# urbansensor.net
KiCad netlist of a schematic drawn in EAGLE
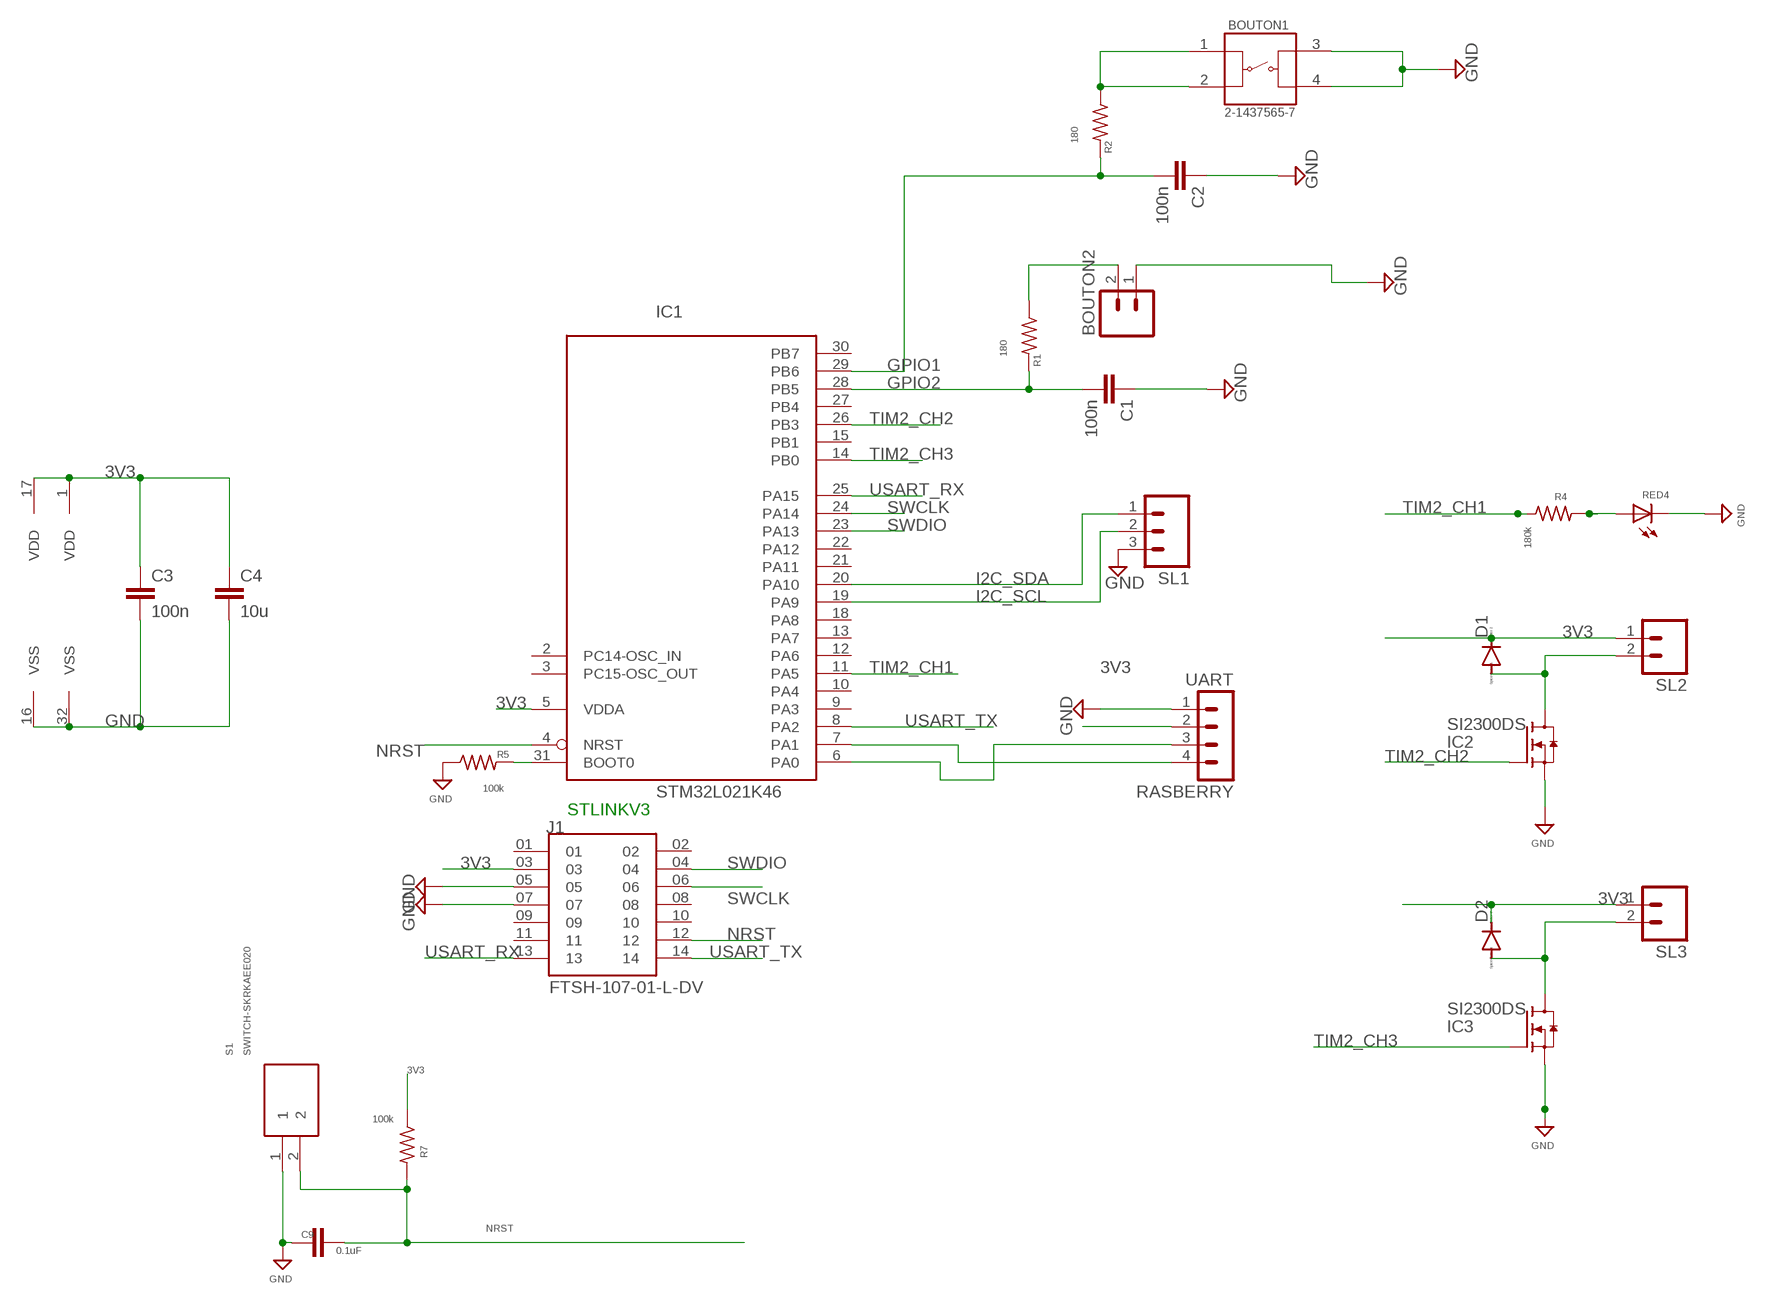
[diagram p0: schematic, sheet 1]

(export (version "E")
  (design (tool "Eeschema 10.0.6"))
  (components
    (comp (ref "BOUTON1")
      (value "2-1437565-7")
      (footprint "eagle-import:SW_2-1437565-7")
      (fields (field (name "MF") "TE Connectivity") (field (name "MP") "FSM2JSMA"))
      (libsource (lib "eagle-import") (part "2-1437565-7"))
    )
    (comp (ref "BOUTON2")
      (value "MA02")
      (footprint "eagle-import:02PA")
      (libsource (lib "eagle-import") (part "MA02"))
    )
    (comp (ref "C1")
      (value "100n")
      (footprint "eagle-import:C0805")
      (libsource (lib "eagle-import") (part "C-EUC0805"))
    )
    (comp (ref "C2")
      (value "100n")
      (footprint "eagle-import:C0805")
      (libsource (lib "eagle-import") (part "C-EUC0805"))
    )
    (comp (ref "C3")
      (value "100n")
      (footprint "eagle-import:C0805")
      (libsource (lib "eagle-import") (part "C-EUC0805"))
    )
    (comp (ref "C4")
      (value "10u")
      (footprint "eagle-import:C1210")
      (libsource (lib "eagle-import") (part "C-EUC1210"))
    )
    (comp (ref "C9")
      (value "0.1uF")
      (footprint "eagle-import:1206")
      (libsource (lib "eagle-import") (part "PASSIF-CAP-1206"))
    )
    (comp (ref "D1")
      (value "DIODE-SOD523")
      (footprint "eagle-import:SOD523")
      (libsource (lib "eagle-import") (part "DIODE-SOD523"))
    )
    (comp (ref "D2")
      (value "DIODE-SOD523")
      (footprint "eagle-import:SOD523")
      (libsource (lib "eagle-import") (part "DIODE-SOD523"))
    )
    (comp (ref "IC1")
      (value "STM32L021K46")
      (footprint "eagle-import:LQFP32")
      (libsource (lib "eagle-import") (part "STM32L021K46"))
    )
    (comp (ref "IC2")
      (value "SI2300DS")
      (footprint "eagle-import:SOT23")
      (libsource (lib "eagle-import") (part "SI2300DS"))
    )
    (comp (ref "IC3")
      (value "SI2300DS")
      (footprint "eagle-import:SOT23")
      (libsource (lib "eagle-import") (part "SI2300DS"))
    )
    (comp (ref "J1")
      (value "FTSH-107-01-L-DV")
      (footprint "eagle-import:SAMTEC_FTSH-107-01-L-DV")
      (fields (field (name "MF") "Samtec"))
      (libsource (lib "eagle-import") (part "FTSH-107-01-L-DV"))
    )
    (comp (ref "R1")
      (value "180")
      (footprint "eagle-import:R0805")
      (libsource (lib "eagle-import") (part "R-US0805"))
    )
    (comp (ref "R2")
      (value "180")
      (footprint "eagle-import:R0805")
      (libsource (lib "eagle-import") (part "R-US0805"))
    )
    (comp (ref "R4")
      (value "180k")
      (footprint "eagle-import:R0805")
      (libsource (lib "eagle-import") (part "R-US0805"))
    )
    (comp (ref "R5")
      (value "100k")
      (footprint "eagle-import:R0805")
      (libsource (lib "eagle-import") (part "R-US0805"))
    )
    (comp (ref "R7")
      (value "100k")
      (footprint "eagle-import:R0805")
      (libsource (lib "eagle-import") (part "R-US0805"))
    )
    (comp (ref "RASBERRY")
      (value "UART")
      (footprint "eagle-import:MA04-1")
      (libsource (lib "eagle-import") (part "MA04-1"))
    )
    (comp (ref "RED4")
      (value "LED-0603")
      (footprint "eagle-import:0603-LED")
      (libsource (lib "eagle-import") (part "LED-0603"))
    )
    (comp (ref "S1")
      (value "SWITCH-SKRKAEE020")
      (footprint "eagle-import:SKRKAEE020")
      (fields
        (field (name "MANUFACTURER_PART_NUMBER") "SKRKAEE020")
        (field (name "MOUSER_PART_NUMBER") "688-SKRKAEE020")
      )
      (libsource (lib "eagle-import") (part "SWITCH-SKRKAEE020"))
    )
    (comp (ref "SL1")
      (value "MA03")
      (footprint "eagle-import:03P")
      (libsource (lib "eagle-import") (part "MA03"))
    )
    (comp (ref "SL2")
      (value "MA02")
      (footprint "eagle-import:02PA")
      (libsource (lib "eagle-import") (part "MA02"))
    )
    (comp (ref "SL3")
      (value "MA02")
      (footprint "eagle-import:02PA")
      (libsource (lib "eagle-import") (part "MA02"))
    )
  )
  (nets
    (net (code "1") (name "/3V3") (class "Default")
      (node (ref "C3") (pin "1") (pinfunction "1_1") (pintype "passive"))
      (node (ref "C4") (pin "1") (pinfunction "1_1") (pintype "passive"))
      (node (ref "D1") (pin "C") (pinfunction "C_C") (pintype "passive"))
      (node (ref "D2") (pin "C") (pinfunction "C_C") (pintype "passive"))
      (node (ref "IC1") (pin "1") (pinfunction "VDD_1") (pintype "power_in"))
      (node (ref "IC1") (pin "17") (pinfunction "VDD_17") (pintype "power_in"))
      (node (ref "IC1") (pin "5") (pinfunction "VDDA_5") (pintype "power_in"))
      (node (ref "J1") (pin "03") (pinfunction "03_03") (pintype "passive"))
      (node (ref "R7") (pin "1") (pinfunction "1_1") (pintype "passive"))
      (node (ref "RASBERRY") (pin "2") (pinfunction "2_2") (pintype "passive"))
      (node (ref "SL2") (pin "1") (pinfunction "1_1") (pintype "passive"))
      (node (ref "SL3") (pin "1") (pinfunction "1_1") (pintype "passive"))
    )
    (net (code "2") (name "/GPIO1") (class "Default")
      (node (ref "C2") (pin "2") (pinfunction "2_2") (pintype "passive"))
      (node (ref "IC1") (pin "29") (pinfunction "PB6_29") (pintype "bidirectional"))
      (node (ref "R2") (pin "2") (pinfunction "2_2") (pintype "passive"))
    )
    (net (code "3") (name "/GPIO2") (class "Default")
      (node (ref "C1") (pin "2") (pinfunction "2_2") (pintype "passive"))
      (node (ref "IC1") (pin "28") (pinfunction "PB5_28") (pintype "bidirectional"))
      (node (ref "R1") (pin "2") (pinfunction "2_2") (pintype "passive"))
    )
    (net (code "4") (name "/I2C_SCL") (class "Default")
      (node (ref "IC1") (pin "19") (pinfunction "PA9_19") (pintype "bidirectional"))
      (node (ref "SL1") (pin "2") (pinfunction "2_2") (pintype "passive"))
    )
    (net (code "5") (name "/I2C_SDA") (class "Default")
      (node (ref "IC1") (pin "20") (pinfunction "PA10_20") (pintype "bidirectional"))
      (node (ref "SL1") (pin "1") (pinfunction "1_1") (pintype "passive"))
    )
    (net (code "6") (name "/NRST") (class "Default")
      (node (ref "C9") (pin "2") (pinfunction "2_2") (pintype "passive"))
      (node (ref "IC1") (pin "4") (pinfunction "NRST_4") (pintype "bidirectional"))
      (node (ref "J1") (pin "12") (pinfunction "12_12") (pintype "passive"))
      (node (ref "R7") (pin "2") (pinfunction "2_2") (pintype "passive"))
      (node (ref "S1") (pin "2") (pinfunction "2_2") (pintype "bidirectional"))
    )
    (net (code "7") (name "/SWCLK") (class "Default")
      (node (ref "IC1") (pin "24") (pinfunction "PA14_24") (pintype "bidirectional"))
      (node (ref "J1") (pin "06") (pinfunction "06_06") (pintype "passive"))
    )
    (net (code "8") (name "/SWDIO") (class "Default")
      (node (ref "IC1") (pin "23") (pinfunction "PA13_23") (pintype "bidirectional"))
      (node (ref "J1") (pin "04") (pinfunction "04_04") (pintype "passive"))
    )
    (net (code "9") (name "/TIM2_CH1") (class "Default")
      (node (ref "IC1") (pin "11") (pinfunction "PA5_11") (pintype "bidirectional"))
      (node (ref "R4") (pin "1") (pinfunction "1_1") (pintype "passive"))
    )
    (net (code "10") (name "/TIM2_CH2") (class "Default")
      (node (ref "IC1") (pin "26") (pinfunction "PB3_26") (pintype "bidirectional"))
      (node (ref "IC2") (pin "1") (pinfunction "G_1") (pintype "passive"))
    )
    (net (code "11") (name "/TIM2_CH3") (class "Default")
      (node (ref "IC1") (pin "14") (pinfunction "PB0_14") (pintype "bidirectional"))
      (node (ref "IC3") (pin "1") (pinfunction "G_1") (pintype "passive"))
    )
    (net (code "12") (name "/USART_RX") (class "Default")
      (node (ref "IC1") (pin "25") (pinfunction "PA15_25") (pintype "bidirectional"))
      (node (ref "J1") (pin "13") (pinfunction "13_13") (pintype "passive"))
    )
    (net (code "13") (name "/USART_TX") (class "Default")
      (node (ref "IC1") (pin "8") (pinfunction "PA2_8") (pintype "bidirectional"))
      (node (ref "J1") (pin "14") (pinfunction "14_14") (pintype "passive"))
    )
    (net (code "14") (name "GND") (class "Default")
      (node (ref "BOUTON1") (pin "3") (pinfunction "3_3") (pintype "passive"))
      (node (ref "BOUTON1") (pin "4") (pinfunction "4_4") (pintype "passive"))
      (node (ref "BOUTON2") (pin "1") (pinfunction "1_1") (pintype "passive"))
      (node (ref "C1") (pin "1") (pinfunction "1_1") (pintype "passive"))
      (node (ref "C2") (pin "1") (pinfunction "1_1") (pintype "passive"))
      (node (ref "C3") (pin "2") (pinfunction "2_2") (pintype "passive"))
      (node (ref "C4") (pin "2") (pinfunction "2_2") (pintype "passive"))
      (node (ref "C9") (pin "1") (pinfunction "1_1") (pintype "passive"))
      (node (ref "IC1") (pin "16") (pinfunction "VSS_16") (pintype "power_in"))
      (node (ref "IC1") (pin "32") (pinfunction "VSS_32") (pintype "power_in"))
      (node (ref "IC2") (pin "2") (pinfunction "S_2") (pintype "passive"))
      (node (ref "IC3") (pin "2") (pinfunction "S_2") (pintype "passive"))
      (node (ref "J1") (pin "05") (pinfunction "05_05") (pintype "passive"))
      (node (ref "J1") (pin "07") (pinfunction "07_07") (pintype "passive"))
      (node (ref "R5") (pin "1") (pinfunction "1_1") (pintype "passive"))
      (node (ref "RASBERRY") (pin "1") (pinfunction "1_1") (pintype "passive"))
      (node (ref "RED4") (pin "C") (pinfunction "C_C") (pintype "passive"))
      (node (ref "S1") (pin "1") (pinfunction "1_1") (pintype "bidirectional"))
      (node (ref "SL1") (pin "3") (pinfunction "3_3") (pintype "passive"))
    )
    (net (code "15") (name "Net-(BOUTON1-Pad1)") (class "Default")
      (node (ref "BOUTON1") (pin "1") (pinfunction "1_1") (pintype "passive"))
      (node (ref "BOUTON1") (pin "2") (pinfunction "2_2") (pintype "passive"))
      (node (ref "R2") (pin "1") (pinfunction "1_1") (pintype "passive"))
    )
    (net (code "16") (name "Net-(BOUTON2-Pad2)") (class "Default")
      (node (ref "BOUTON2") (pin "2") (pinfunction "2_2") (pintype "passive"))
      (node (ref "R1") (pin "1") (pinfunction "1_1") (pintype "passive"))
    )
    (net (code "17") (name "Net-(IC1A-BOOT0)") (class "Default")
      (node (ref "IC1") (pin "31") (pinfunction "BOOT0_31") (pintype "input"))
      (node (ref "R5") (pin "2") (pinfunction "2_2") (pintype "passive"))
    )
    (net (code "18") (name "Net-(IC1A-PA0)") (class "Default")
      (node (ref "IC1") (pin "6") (pinfunction "PA0_6") (pintype "bidirectional"))
      (node (ref "RASBERRY") (pin "3") (pinfunction "3_3") (pintype "passive"))
    )
    (net (code "19") (name "Net-(IC1A-PA1)") (class "Default")
      (node (ref "IC1") (pin "7") (pinfunction "PA1_7") (pintype "bidirectional"))
      (node (ref "RASBERRY") (pin "4") (pinfunction "4_4") (pintype "passive"))
    )
    (net (code "20") (name "Net-(IC2-D)") (class "Default")
      (node (ref "D1") (pin "A") (pinfunction "A_A") (pintype "passive"))
      (node (ref "IC2") (pin "3") (pinfunction "D_3") (pintype "passive"))
      (node (ref "SL2") (pin "2") (pinfunction "2_2") (pintype "passive"))
    )
    (net (code "21") (name "Net-(IC3-D)") (class "Default")
      (node (ref "D2") (pin "A") (pinfunction "A_A") (pintype "passive"))
      (node (ref "IC3") (pin "3") (pinfunction "D_3") (pintype "passive"))
      (node (ref "SL3") (pin "2") (pinfunction "2_2") (pintype "passive"))
    )
    (net (code "22") (name "Net-(R4-Pad2)") (class "Default")
      (node (ref "R4") (pin "2") (pinfunction "2_2") (pintype "passive"))
      (node (ref "RED4") (pin "A") (pinfunction "A_A") (pintype "passive"))
    )
    (net (code "23") (name "unconnected-(IC1A-PA3-Pad9)") (class "Default")
      (node (ref "IC1") (pin "9") (pinfunction "PA3_9") (pintype "bidirectional"))
    )
    (net (code "24") (name "unconnected-(IC1A-PA4-Pad10)") (class "Default")
      (node (ref "IC1") (pin "10") (pinfunction "PA4_10") (pintype "bidirectional"))
    )
    (net (code "25") (name "unconnected-(IC1A-PA6-Pad12)") (class "Default")
      (node (ref "IC1") (pin "12") (pinfunction "PA6_12") (pintype "bidirectional"))
    )
    (net (code "26") (name "unconnected-(IC1A-PA7-Pad13)") (class "Default")
      (node (ref "IC1") (pin "13") (pinfunction "PA7_13") (pintype "bidirectional"))
    )
    (net (code "27") (name "unconnected-(IC1A-PA8-Pad18)") (class "Default")
      (node (ref "IC1") (pin "18") (pinfunction "PA8_18") (pintype "bidirectional"))
    )
    (net (code "28") (name "unconnected-(IC1A-PA11-Pad21)") (class "Default")
      (node (ref "IC1") (pin "21") (pinfunction "PA11_21") (pintype "bidirectional"))
    )
    (net (code "29") (name "unconnected-(IC1A-PA12-Pad22)") (class "Default")
      (node (ref "IC1") (pin "22") (pinfunction "PA12_22") (pintype "bidirectional"))
    )
    (net (code "30") (name "unconnected-(IC1A-PB1-Pad15)") (class "Default")
      (node (ref "IC1") (pin "15") (pinfunction "PB1_15") (pintype "bidirectional"))
    )
    (net (code "31") (name "unconnected-(IC1A-PB4-Pad27)") (class "Default")
      (node (ref "IC1") (pin "27") (pinfunction "PB4_27") (pintype "bidirectional"))
    )
    (net (code "32") (name "unconnected-(IC1A-PB7-Pad30)") (class "Default")
      (node (ref "IC1") (pin "30") (pinfunction "PB7_30") (pintype "bidirectional"))
    )
    (net (code "33") (name "unconnected-(IC1A-PC14-OSC_IN-Pad2)") (class "Default")
      (node (ref "IC1") (pin "2") (pinfunction "PC14-OSC_IN_2") (pintype "bidirectional"))
    )
    (net (code "34") (name "unconnected-(IC1A-PC15-OSC_OUT-Pad3)") (class "Default")
      (node (ref "IC1") (pin "3") (pinfunction "PC15-OSC_OUT_3") (pintype "bidirectional"))
    )
    (net (code "35") (name "unconnected-(J1-Pad01)") (class "Default")
      (node (ref "J1") (pin "01") (pinfunction "01_01") (pintype "passive"))
    )
    (net (code "36") (name "unconnected-(J1-Pad02)") (class "Default")
      (node (ref "J1") (pin "02") (pinfunction "02_02") (pintype "passive"))
    )
    (net (code "37") (name "unconnected-(J1-Pad08)") (class "Default")
      (node (ref "J1") (pin "08") (pinfunction "08_08") (pintype "passive"))
    )
    (net (code "38") (name "unconnected-(J1-Pad09)") (class "Default")
      (node (ref "J1") (pin "09") (pinfunction "09_09") (pintype "passive"))
    )
    (net (code "39") (name "unconnected-(J1-Pad10)") (class "Default")
      (node (ref "J1") (pin "10") (pinfunction "10_10") (pintype "passive"))
    )
    (net (code "40") (name "unconnected-(J1-Pad11)") (class "Default")
      (node (ref "J1") (pin "11") (pinfunction "11_11") (pintype "passive"))
    )
  )
)
